# sineGenerator.net
KiCad netlist of a schematic drawn in EAGLE
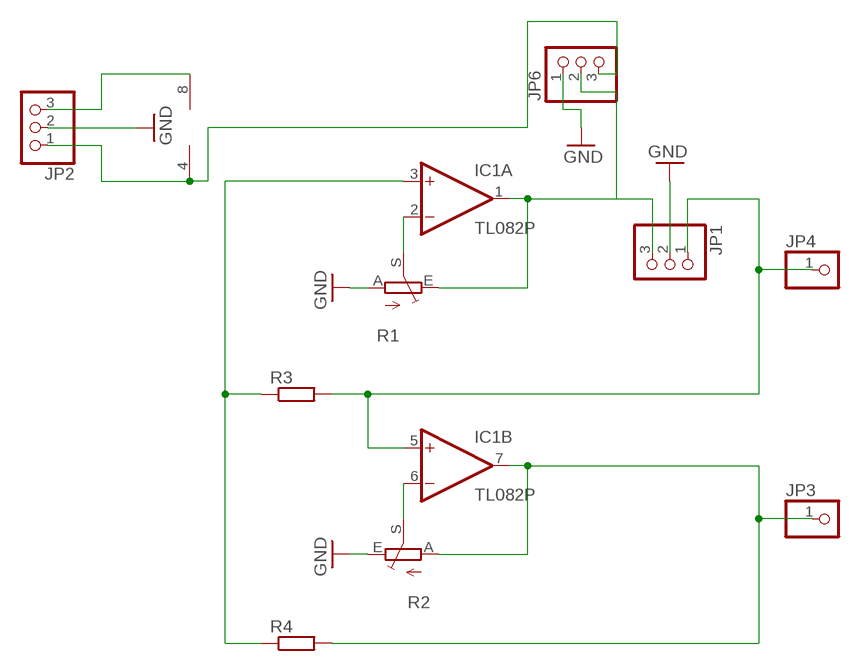
[diagram p0: schematic, sheet 1]

(export (version "E")
  (design (tool "Eeschema 10.0.6"))
  (components
    (comp (ref "IC1")
      (value "TL082P")
      (footprint "eagle-import:DIL08")
      (libsource (lib "eagle-import") (part "TL082P"))
    )
    (comp (ref "JP1")
      (value "PINHD-1X3")
      (footprint "eagle-import:1X03")
      (libsource (lib "eagle-import") (part "PINHD-1X3"))
    )
    (comp (ref "JP2")
      (value "PINHD-1X3")
      (footprint "eagle-import:1X03")
      (libsource (lib "eagle-import") (part "PINHD-1X3"))
    )
    (comp (ref "JP3")
      (value "PINHD-1X1")
      (footprint "eagle-import:1X01")
      (libsource (lib "eagle-import") (part "PINHD-1X1"))
    )
    (comp (ref "JP4")
      (value "PINHD-1X1")
      (footprint "eagle-import:1X01")
      (libsource (lib "eagle-import") (part "PINHD-1X1"))
    )
    (comp (ref "JP6")
      (value "PINHD-1X3")
      (footprint "eagle-import:1X03")
      (libsource (lib "eagle-import") (part "PINHD-1X3"))
    )
    (comp (ref "R1")
      (value "TRIM_EU-CA9V")
      (footprint "eagle-import:CA9V")
      (libsource (lib "eagle-import") (part "TRIM_EU-CA9V"))
    )
    (comp (ref "R2")
      (value "TRIM_EU-CA9V")
      (footprint "eagle-import:CA9V")
      (libsource (lib "eagle-import") (part "TRIM_EU-CA9V"))
    )
    (comp (ref "R3")
      (value "R-EU_0204/2V")
      (footprint "eagle-import:0204V")
      (libsource (lib "eagle-import") (part "R-EU_0204/2V"))
    )
    (comp (ref "R4")
      (value "R-EU_0204/2V")
      (footprint "eagle-import:0204V")
      (libsource (lib "eagle-import") (part "R-EU_0204/2V"))
    )
  )
  (nets
    (net (code "1") (name "GND") (class "Default")
      (node (ref "JP1") (pin "2") (pinfunction "2_2") (pintype "passive"))
      (node (ref "JP2") (pin "2") (pinfunction "2_2") (pintype "passive"))
      (node (ref "JP6") (pin "1") (pinfunction "1_1") (pintype "passive"))
      (node (ref "R1") (pin "A") (pinfunction "A_A") (pintype "passive"))
      (node (ref "R2") (pin "E") (pinfunction "E_E") (pintype "passive"))
    )
    (net (code "2") (name "Net-(IC1A-+IN)") (class "Default")
      (node (ref "IC1") (pin "3") (pinfunction "+IN_3") (pintype "input"))
      (node (ref "R3") (pin "1") (pinfunction "1_1") (pintype "passive"))
      (node (ref "R4") (pin "1") (pinfunction "1_1") (pintype "passive"))
    )
    (net (code "3") (name "Net-(IC1A--IN)") (class "Default")
      (node (ref "IC1") (pin "2") (pinfunction "-IN_2") (pintype "input"))
      (node (ref "R1") (pin "S") (pinfunction "S_S") (pintype "passive"))
    )
    (net (code "4") (name "Net-(IC1A-OUT)") (class "Default")
      (node (ref "IC1") (pin "1") (pinfunction "OUT_1") (pintype "output"))
      (node (ref "JP1") (pin "3") (pinfunction "3_3") (pintype "passive"))
      (node (ref "JP6") (pin "2") (pinfunction "2_2") (pintype "passive"))
      (node (ref "R1") (pin "E") (pinfunction "E_E") (pintype "passive"))
    )
    (net (code "5") (name "Net-(IC1B-+IN)") (class "Default")
      (node (ref "IC1") (pin "5") (pinfunction "+IN_5") (pintype "input"))
      (node (ref "JP1") (pin "1") (pinfunction "1_1") (pintype "passive"))
      (node (ref "JP4") (pin "1") (pinfunction "1_1") (pintype "passive"))
      (node (ref "R3") (pin "2") (pinfunction "2_2") (pintype "passive"))
    )
    (net (code "6") (name "Net-(IC1B--IN)") (class "Default")
      (node (ref "IC1") (pin "6") (pinfunction "-IN_6") (pintype "input"))
      (node (ref "R2") (pin "S") (pinfunction "S_S") (pintype "passive"))
    )
    (net (code "7") (name "Net-(IC1B-OUT)") (class "Default")
      (node (ref "IC1") (pin "7") (pinfunction "OUT_7") (pintype "output"))
      (node (ref "JP3") (pin "1") (pinfunction "1_1") (pintype "passive"))
      (node (ref "R2") (pin "A") (pinfunction "A_A") (pintype "passive"))
      (node (ref "R4") (pin "2") (pinfunction "2_2") (pintype "passive"))
    )
    (net (code "8") (name "Net-(IC1C-V+)") (class "Default")
      (node (ref "IC1") (pin "8") (pinfunction "V+_8") (pintype "power_in"))
      (node (ref "JP2") (pin "3") (pinfunction "3_3") (pintype "passive"))
    )
    (net (code "9") (name "Net-(IC1C-V-)") (class "Default")
      (node (ref "IC1") (pin "4") (pinfunction "V-_4") (pintype "power_in"))
      (node (ref "JP2") (pin "1") (pinfunction "1_1") (pintype "passive"))
      (node (ref "JP6") (pin "3") (pinfunction "3_3") (pintype "passive"))
    )
  )
)
